# pc_kalam_v3.net
KiCad netlist of a schematic drawn in EAGLE
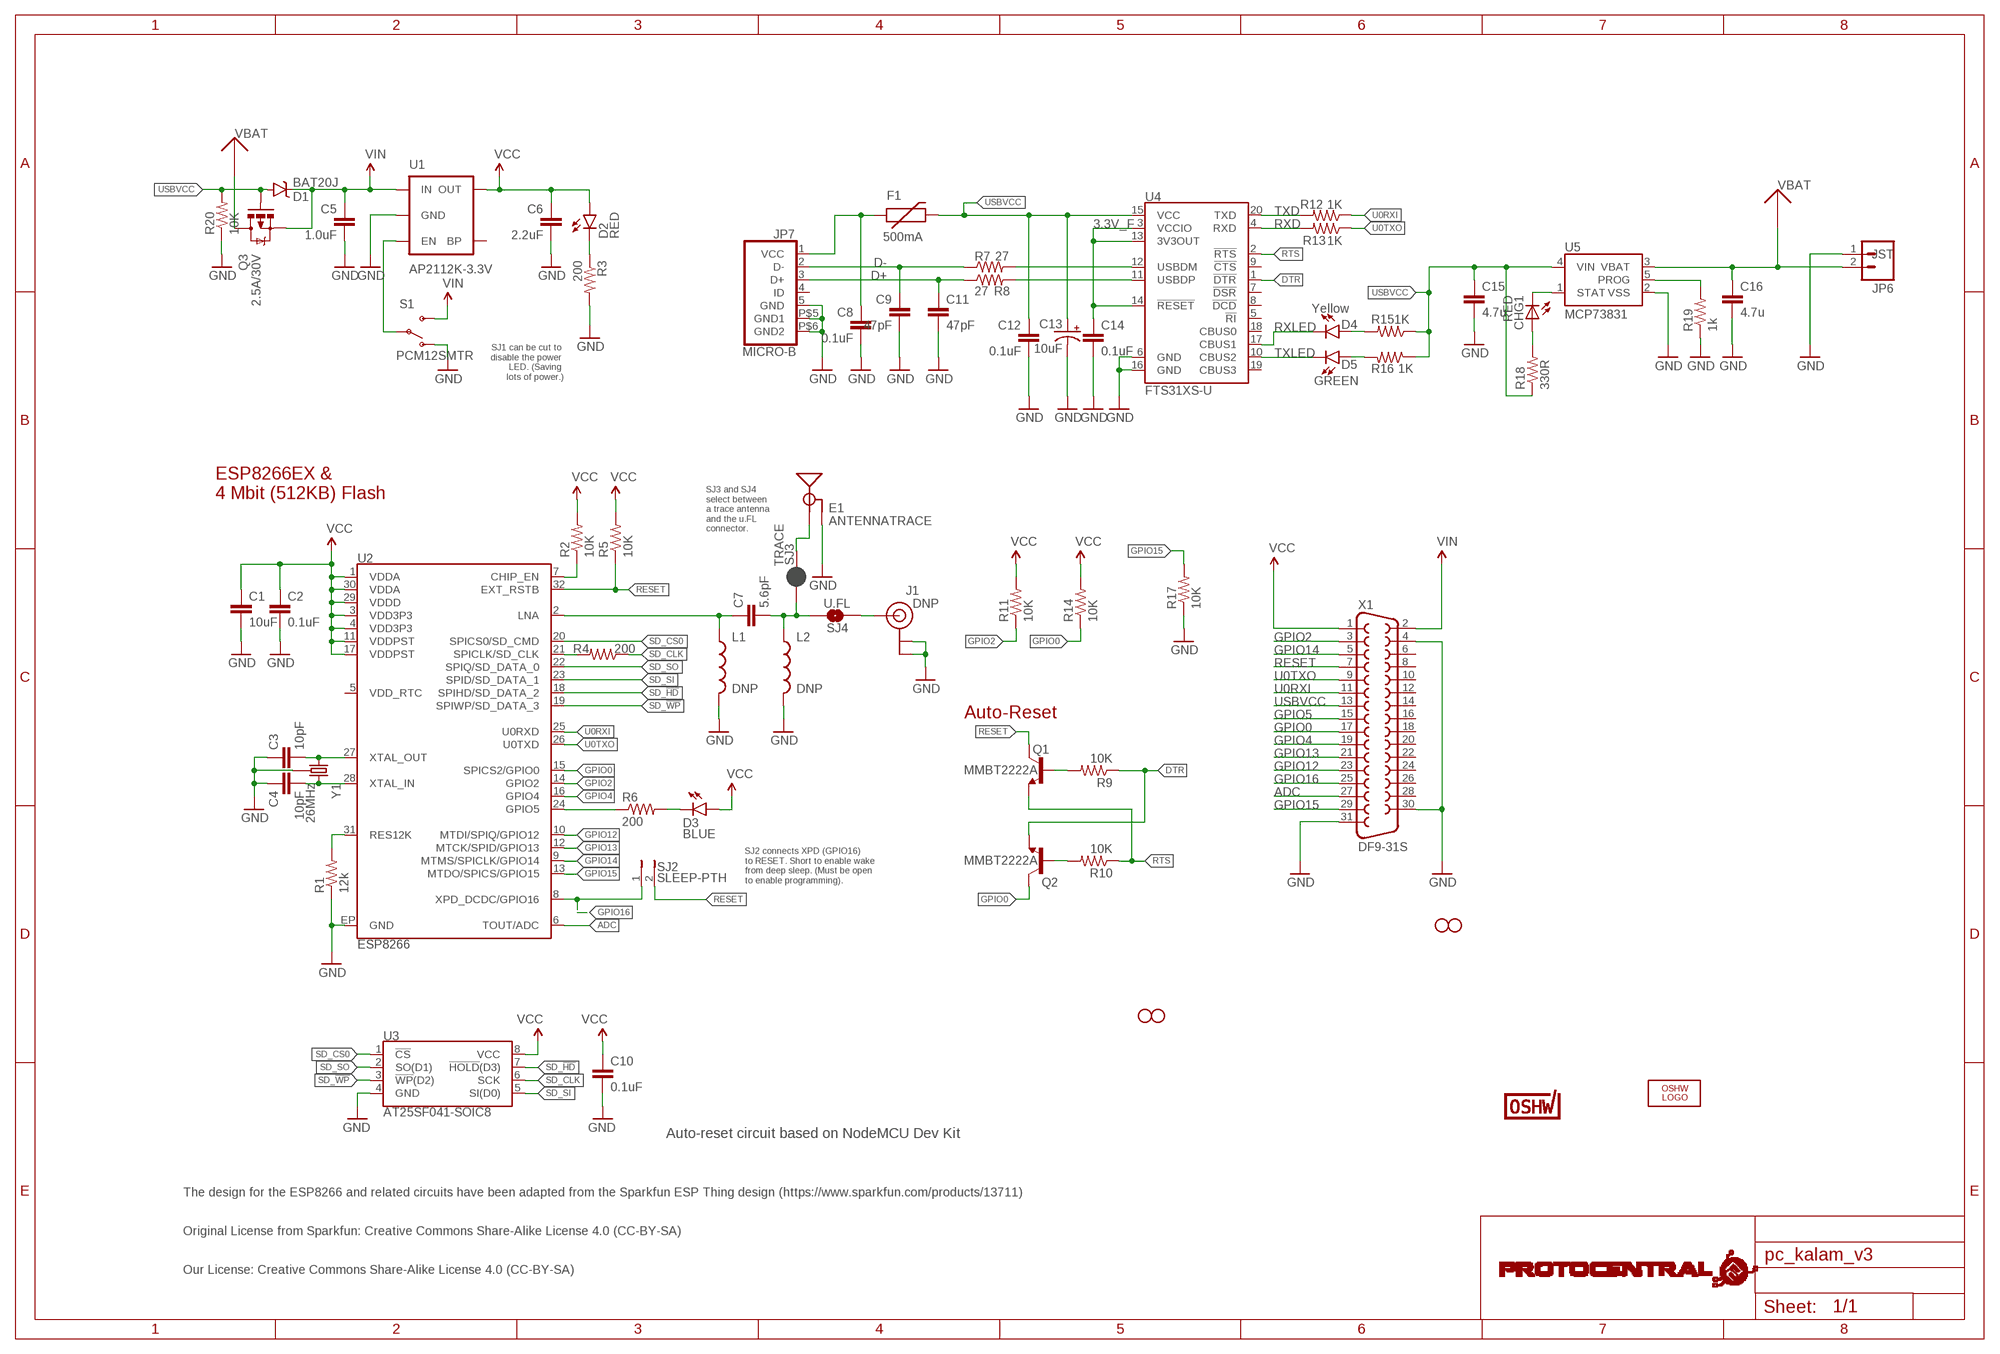
[diagram p0: schematic, sheet 1]

(export (version "E")
  (design (tool "Eeschema 10.0.6"))
  (components
    (comp (ref "C1")
      (value "10uF")
      (footprint "eagle-import:0603-CAP")
      (libsource (lib "eagle-import") (part "10UF-6.3V-20%(0603)"))
    )
    (comp (ref "C2")
      (value "0.1uF")
      (footprint "eagle-import:0603-CAP")
      (libsource (lib "eagle-import") (part "0.1UF-25V(+80/-20%)(0603)"))
    )
    (comp (ref "C3")
      (value "10pF")
      (footprint "eagle-import:0603-CAP")
      (libsource (lib "eagle-import") (part "10PF-50V-5%(0603)"))
    )
    (comp (ref "C4")
      (value "10pF")
      (footprint "eagle-import:0603-CAP")
      (libsource (lib "eagle-import") (part "10PF-50V-5%(0603)"))
    )
    (comp (ref "C5")
      (value "1.0uF")
      (footprint "eagle-import:0805")
      (libsource (lib "eagle-import") (part "1.0UF-25V-+80/-20(0805)"))
    )
    (comp (ref "C6")
      (value "2.2uF")
      (footprint "eagle-import:0603-CAP")
      (libsource (lib "eagle-import") (part "2.2UF-10V-20%(0603)"))
    )
    (comp (ref "C7")
      (value "5.6pF")
      (footprint "eagle-import:0603-CAP")
      (libsource (lib "eagle-import") (part "CAP0603-CAP"))
    )
    (comp (ref "C8")
      (value "0.1uF")
      (footprint "eagle-import:C0402")
      (libsource (lib "eagle-import") (part "C-EUC0402"))
    )
    (comp (ref "C9")
      (value "47pF")
      (footprint "eagle-import:0603-CAP")
      (libsource (lib "eagle-import") (part "47PF-50V-5%(0603)"))
    )
    (comp (ref "C10")
      (value "0.1uF")
      (footprint "eagle-import:0603-CAP")
      (libsource (lib "eagle-import") (part "0.1UF-25V(+80/-20%)(0603)"))
    )
    (comp (ref "C11")
      (value "47pF")
      (footprint "eagle-import:0603-CAP")
      (libsource (lib "eagle-import") (part "47PF-50V-5%(0603)"))
    )
    (comp (ref "C12")
      (value "0.1uF")
      (footprint "eagle-import:0603-CAP")
      (libsource (lib "eagle-import") (part "0.1UF-25V(+80/-20%)(0603)"))
    )
    (comp (ref "C13")
      (value "10uF")
      (footprint "eagle-import:EIA3216")
      (libsource (lib "eagle-import") (part "10UF-16V-10%(TANT)"))
    )
    (comp (ref "C14")
      (value "0.1uF")
      (footprint "eagle-import:0603-CAP")
      (libsource (lib "eagle-import") (part "0.1UF-25V(+80/-20%)(0603)"))
    )
    (comp (ref "C15")
      (value "4.7u")
      (footprint "eagle-import:C0805")
      (libsource (lib "eagle-import") (part "C-EUC0805"))
    )
    (comp (ref "C16")
      (value "4.7u")
      (footprint "eagle-import:C0805")
      (libsource (lib "eagle-import") (part "C-EUC0805"))
    )
    (comp (ref "CHG1")
      (value "RED")
      (footprint "eagle-import:CHIPLED_0603")
      (libsource (lib "eagle-import") (part "LEDCHIPLED_0603"))
    )
    (comp (ref "D1")
      (value "BAT20J")
      (footprint "eagle-import:SOD-323")
      (libsource (lib "eagle-import") (part "DIODE-SCHOTTKY-BAT20J"))
    )
    (comp (ref "D2")
      (value "RED")
      (footprint "eagle-import:LED-0603")
      (libsource (lib "eagle-import") (part "LED-RED0603"))
    )
    (comp (ref "D3")
      (value "BLUE")
      (footprint "eagle-import:LED-0603")
      (libsource (lib "eagle-import") (part "LED-BLUE0603"))
    )
    (comp (ref "D4")
      (value "Yellow")
      (footprint "eagle-import:LED-0603")
      (libsource (lib "eagle-import") (part "LED-YELLOW0603"))
    )
    (comp (ref "D5")
      (value "GREEN")
      (footprint "eagle-import:LED-0603")
      (libsource (lib "eagle-import") (part "LED-GREEN0603"))
    )
    (comp (ref "E1")
      (value "ANTENNATRACE")
      (footprint "eagle-import:TRACE_ANTENNA_2.4GHZ_25.7MM")
      (libsource (lib "eagle-import") (part "ANTENNATRACE"))
    )
    (comp (ref "F1")
      (value "500mA")
      (footprint "eagle-import:PTC-1206")
      (libsource (lib "eagle-import") (part "PTCSMD"))
    )
    (comp (ref "J1")
      (value "DNP")
      (footprint "eagle-import:U.FL")
      (libsource (lib "eagle-import") (part "U.FL"))
    )
    (comp (ref "JP6")
      (value "M02-JST-2MM-SMT")
      (footprint "eagle-import:JST-2-SMD")
      (libsource (lib "eagle-import") (part "M02-JST-2MM-SMT"))
    )
    (comp (ref "JP7")
      (value "MICRO-B")
      (footprint "eagle-import:MICRO-B")
      (libsource (lib "eagle-import") (part "MICRO-B"))
    )
    (comp (ref "L1")
      (value "DNP")
      (footprint "eagle-import:0603")
      (libsource (lib "eagle-import") (part "INDUCTOR0603"))
    )
    (comp (ref "L2")
      (value "DNP")
      (footprint "eagle-import:0603")
      (libsource (lib "eagle-import") (part "INDUCTOR0603"))
    )
    (comp (ref "LOGO2")
      (value "OSHW_LOGO_FILLX0200-NT")
      (footprint "eagle-import:OSHW_FILLX200_NOTEXT")
      (libsource (lib "eagle-import") (part "OSHW_LOGO_FILLX0200-NT"))
    )
    (comp (ref "Q1")
      (value "MMBT2222A")
      (footprint "eagle-import:SOT23-3@1")
      (libsource (lib "eagle-import") (part "TRANSISTOR_NPNMMBT2222A"))
    )
    (comp (ref "Q2")
      (value "MMBT2222A")
      (footprint "eagle-import:SOT23-3@1")
      (libsource (lib "eagle-import") (part "TRANSISTOR_NPNMMBT2222A"))
    )
    (comp (ref "Q3")
      (value "2.5A/30V")
      (footprint "eagle-import:SOT23-3")
      (libsource (lib "eagle-import") (part "MOSFET-PCHANNELDMG2307L"))
    )
    (comp (ref "R1")
      (value "12k")
      (footprint "eagle-import:0603-RES")
      (libsource (lib "eagle-import") (part "12KOHM-1/10W-1%(0603)"))
    )
    (comp (ref "R2")
      (value "10K")
      (footprint "eagle-import:0603-RES")
      (libsource (lib "eagle-import") (part "10KOHM1/10W1%(0603)0603"))
    )
    (comp (ref "R3")
      (value "200")
      (footprint "eagle-import:0603-RES")
      (libsource (lib "eagle-import") (part "200OHM1/10W1%(0603)"))
    )
    (comp (ref "R4")
      (value "200")
      (footprint "eagle-import:0603-RES")
      (libsource (lib "eagle-import") (part "200OHM1/10W1%(0603)"))
    )
    (comp (ref "R5")
      (value "10K")
      (footprint "eagle-import:0603-RES")
      (libsource (lib "eagle-import") (part "10KOHM1/10W1%(0603)0603"))
    )
    (comp (ref "R6")
      (value "200")
      (footprint "eagle-import:0603-RES")
      (libsource (lib "eagle-import") (part "200OHM1/10W1%(0603)"))
    )
    (comp (ref "R7")
      (value "27")
      (footprint "eagle-import:0603-RES")
      (libsource (lib "eagle-import") (part "27OHM1/10W1%(0603)0603-RES"))
    )
    (comp (ref "R8")
      (value "27")
      (footprint "eagle-import:0603-RES")
      (libsource (lib "eagle-import") (part "27OHM1/10W1%(0603)0603-RES"))
    )
    (comp (ref "R9")
      (value "10K")
      (footprint "eagle-import:0603-RES")
      (libsource (lib "eagle-import") (part "10KOHM1/10W1%(0603)0603"))
    )
    (comp (ref "R10")
      (value "10K")
      (footprint "eagle-import:0603-RES")
      (libsource (lib "eagle-import") (part "10KOHM1/10W1%(0603)0603"))
    )
    (comp (ref "R11")
      (value "10K")
      (footprint "eagle-import:0603-RES")
      (libsource (lib "eagle-import") (part "10KOHM1/10W1%(0603)0603"))
    )
    (comp (ref "R12")
      (value "1K")
      (footprint "eagle-import:0603-RES")
      (libsource (lib "eagle-import") (part "1KOHM-1/10W-1%(0603)"))
    )
    (comp (ref "R13")
      (value "1K")
      (footprint "eagle-import:0603-RES")
      (libsource (lib "eagle-import") (part "1KOHM-1/10W-1%(0603)"))
    )
    (comp (ref "R14")
      (value "10K")
      (footprint "eagle-import:0603-RES")
      (libsource (lib "eagle-import") (part "10KOHM1/10W1%(0603)0603"))
    )
    (comp (ref "R15")
      (value "1K")
      (footprint "eagle-import:0603-RES")
      (libsource (lib "eagle-import") (part "1KOHM-1/10W-1%(0603)"))
    )
    (comp (ref "R16")
      (value "1K")
      (footprint "eagle-import:0603-RES")
      (libsource (lib "eagle-import") (part "1KOHM-1/10W-1%(0603)"))
    )
    (comp (ref "R17")
      (value "10K")
      (footprint "eagle-import:0603-RES")
      (libsource (lib "eagle-import") (part "10KOHM1/10W1%(0603)0603"))
    )
    (comp (ref "R18")
      (value "330R")
      (footprint "eagle-import:R0402")
      (libsource (lib "eagle-import") (part "R-US_R0402"))
    )
    (comp (ref "R19")
      (value "1k")
      (footprint "eagle-import:R0402")
      (libsource (lib "eagle-import") (part "R-US_R0402"))
    )
    (comp (ref "R20")
      (value "10K")
      (footprint "eagle-import:R0402")
      (libsource (lib "eagle-import") (part "R-US_R0402"))
    )
    (comp (ref "S1")
      (value "PCM12SMTR")
      (footprint "eagle-import:SWITCH-SPST-SMD-A")
      (libsource (lib "eagle-import") (part "SWITCH-SPDT-SMD-A"))
    )
    (comp (ref "SJ2")
      (value "SLEEP-PTH")
      (footprint "eagle-import:PTH-JUMPER-2-NO_NO_SILK")
      (libsource (lib "eagle-import") (part "JUMPER-PTH-2-NO"))
    )
    (comp (ref "SJ3")
      (value "TRACE")
      (footprint "eagle-import:PAD-JUMPER-2-NC_BY_PASTE_NO_SILK")
      (libsource (lib "eagle-import") (part "JUMPER-PAD-2-NC_BY_PASTENO-SILK"))
    )
    (comp (ref "SJ4")
      (value "U.FL")
      (footprint "eagle-import:PAD-JUMPER-2-NO_NO_SILK")
      (libsource (lib "eagle-import") (part "JUMPER-PAD-2-NO"))
    )
    (comp (ref "STANDOFF1")
      (value "STAND-OFF")
      (footprint "eagle-import:STAND-OFF")
      (libsource (lib "eagle-import") (part "STAND-OFF"))
    )
    (comp (ref "STANDOFF2")
      (value "STAND-OFF")
      (footprint "eagle-import:STAND-OFF")
      (libsource (lib "eagle-import") (part "STAND-OFF"))
    )
    (comp (ref "STANDOFF3")
      (value "STAND-OFF")
      (footprint "eagle-import:STAND-OFF")
      (libsource (lib "eagle-import") (part "STAND-OFF"))
    )
    (comp (ref "STANDOFF4")
      (value "STAND-OFF")
      (footprint "eagle-import:STAND-OFF")
      (libsource (lib "eagle-import") (part "STAND-OFF"))
    )
    (comp (ref "U$1")
      (value "PROTY_LOGO_WITH_TEXT")
      (footprint "eagle-import:PROTY_WITH_TEXT")
      (libsource (lib "eagle-import") (part "PROTY_LOGO_WITH_TEXT"))
    )
    (comp (ref "U$5")
      (value "CERT-MEDIUM")
      (footprint "eagle-import:CERT-MED-SILK")
      (libsource (lib "eagle-import") (part "CERT-MEDIUM"))
    )
    (comp (ref "U$8")
      (value "PROTY-LOGO")
      (footprint "eagle-import:LOGO-PROTY")
      (libsource (lib "eagle-import") (part "PROTY-LOGO"))
    )
    (comp (ref "U1")
      (value "AP2112K-3.3V")
      (footprint "eagle-import:SOT23-5")
      (libsource (lib "eagle-import") (part "V_REG_LDOSMD"))
    )
    (comp (ref "U2")
      (value "ESP8266")
      (footprint "eagle-import:QFN32")
      (libsource (lib "eagle-import") (part "ESP8266"))
    )
    (comp (ref "U3")
      (value "AT25SF041-SOIC8")
      (footprint "eagle-import:SO08")
      (libsource (lib "eagle-import") (part "AT25SF041-SOIC8"))
    )
    (comp (ref "U4")
      (value "FTS31XS-U")
      (footprint "eagle-import:SSOP20_L")
      (libsource (lib "eagle-import") (part "FT231XS"))
    )
    (comp (ref "U5")
      (value "MCP73831")
      (footprint "eagle-import:SOT23-5")
      (libsource (lib "eagle-import") (part "MCP73831"))
    )
    (comp (ref "X1")
      (value "DF9-31S")
      (footprint "eagle-import:DF9-31S")
      (fields (field (name "MPN") "DF9-31S-1V(32)"))
      (libsource (lib "eagle-import") (part "DF9-31S"))
    )
    (comp (ref "Y1")
      (value "26MHz")
      (footprint "eagle-import:CRYSTAL-SMD-3.2X2.5")
      (libsource (lib "eagle-import") (part "CRYSTAL-GROUNDED3.2X2.5"))
    )
  )
  (nets
    (net (code "1") (name "/3.3V_F") (class "Default")
      (node (ref "C14") (pin "1") (pinfunction "1_1") (pintype "passive"))
      (node (ref "U4") (pin "13") (pinfunction "3V3OUT_13") (pintype "bidirectional"))
      (node (ref "U4") (pin "14") (pinfunction "~{RESET}_14") (pintype "bidirectional"))
      (node (ref "U4") (pin "3") (pinfunction "VCCIO_3") (pintype "bidirectional"))
    )
    (net (code "2") (name "/D+") (class "Default")
      (node (ref "C11") (pin "1") (pinfunction "1_1") (pintype "passive"))
      (node (ref "JP7") (pin "3") (pinfunction "D+_3") (pintype "bidirectional"))
      (node (ref "R8") (pin "1") (pinfunction "1_1") (pintype "passive"))
    )
    (net (code "3") (name "/D-") (class "Default")
      (node (ref "C9") (pin "1") (pinfunction "1_1") (pintype "passive"))
      (node (ref "JP7") (pin "2") (pinfunction "D-_2") (pintype "bidirectional"))
      (node (ref "R7") (pin "1") (pinfunction "1_1") (pintype "passive"))
    )
    (net (code "4") (name "/GPIO5") (class "Default")
      (node (ref "R6") (pin "1") (pinfunction "1_1") (pintype "passive"))
      (node (ref "U2") (pin "24") (pinfunction "GPIO5_24") (pintype "bidirectional"))
      (node (ref "X1") (pin "15") (pinfunction "15_15") (pintype "passive"))
    )
    (net (code "5") (name "/RXD") (class "Default")
      (node (ref "R13") (pin "2") (pinfunction "2_2") (pintype "passive"))
      (node (ref "U4") (pin "4") (pinfunction "RXD_4") (pintype "bidirectional"))
    )
    (net (code "6") (name "/RXLED") (class "Default")
      (node (ref "D4") (pin "C") (pinfunction "C_C") (pintype "passive"))
      (node (ref "U4") (pin "17") (pinfunction "CBUS1_17") (pintype "bidirectional"))
    )
    (net (code "7") (name "/SD_~{HD}") (class "Default")
      (node (ref "U2") (pin "18") (pinfunction "SPIHD/SD_DATA_2_18") (pintype "bidirectional"))
      (node (ref "U3") (pin "7") (pinfunction "~{HOLD}(D3)_7") (pintype "bidirectional"))
    )
    (net (code "8") (name "/SD_~{WP}") (class "Default")
      (node (ref "U2") (pin "19") (pinfunction "SPIWP/SD_DATA_3_19") (pintype "bidirectional"))
      (node (ref "U3") (pin "3") (pinfunction "~{WP}(D2)_3") (pintype "bidirectional"))
    )
    (net (code "9") (name "/TXD") (class "Default")
      (node (ref "R12") (pin "2") (pinfunction "2_2") (pintype "passive"))
      (node (ref "U4") (pin "20") (pinfunction "TXD_20") (pintype "bidirectional"))
    )
    (net (code "10") (name "/TXLED") (class "Default")
      (node (ref "D5") (pin "C") (pinfunction "C_C") (pintype "passive"))
      (node (ref "U4") (pin "10") (pinfunction "CBUS2_10") (pintype "bidirectional"))
    )
    (net (code "11") (name "ADC") (class "Default")
      (node (ref "U2") (pin "6") (pinfunction "TOUT/ADC_6") (pintype "bidirectional"))
      (node (ref "X1") (pin "27") (pinfunction "27_27") (pintype "passive"))
    )
    (net (code "12") (name "DTR") (class "Default")
      (node (ref "Q2") (pin "2") (pinfunction "E_2") (pintype "passive"))
      (node (ref "R9") (pin "1") (pinfunction "1_1") (pintype "passive"))
      (node (ref "U4") (pin "1") (pinfunction "~{DTR}_1") (pintype "bidirectional"))
    )
    (net (code "13") (name "GND") (class "Default")
      (node (ref "C1") (pin "2") (pinfunction "2_2") (pintype "passive"))
      (node (ref "C10") (pin "2") (pinfunction "2_2") (pintype "passive"))
      (node (ref "C11") (pin "2") (pinfunction "2_2") (pintype "passive"))
      (node (ref "C12") (pin "2") (pinfunction "2_2") (pintype "passive"))
      (node (ref "C13") (pin "C") (pinfunction "-_C") (pintype "passive"))
      (node (ref "C14") (pin "2") (pinfunction "2_2") (pintype "passive"))
      (node (ref "C15") (pin "2") (pinfunction "2_2") (pintype "passive"))
      (node (ref "C16") (pin "2") (pinfunction "2_2") (pintype "passive"))
      (node (ref "C2") (pin "2") (pinfunction "2_2") (pintype "passive"))
      (node (ref "C3") (pin "1") (pinfunction "1_1") (pintype "passive"))
      (node (ref "C4") (pin "1") (pinfunction "1_1") (pintype "passive"))
      (node (ref "C5") (pin "2") (pinfunction "2_2") (pintype "passive"))
      (node (ref "C6") (pin "2") (pinfunction "2_2") (pintype "passive"))
      (node (ref "C8") (pin "2") (pinfunction "2_2") (pintype "passive"))
      (node (ref "C9") (pin "2") (pinfunction "2_2") (pintype "passive"))
      (node (ref "E1") (pin "GND") (pinfunction "GND_GND") (pintype "bidirectional"))
      (node (ref "E1") (pin "GND2") (pinfunction "GND_GND2") (pintype "bidirectional"))
      (node (ref "J1") (pin "P$1") (pinfunction "GND_P$1") (pintype "bidirectional"))
      (node (ref "J1") (pin "P$2") (pinfunction "GND_P$2") (pintype "bidirectional"))
      (node (ref "JP6") (pin "1") (pinfunction "1_1") (pintype "passive"))
      (node (ref "JP7") (pin "5") (pinfunction "GND_5") (pintype "bidirectional"))
      (node (ref "JP7") (pin "P$5") (pinfunction "GND1_P$5") (pintype "bidirectional"))
      (node (ref "JP7") (pin "P$6") (pinfunction "GND2_P$6") (pintype "bidirectional"))
      (node (ref "L1") (pin "2") (pinfunction "2_2") (pintype "passive"))
      (node (ref "L2") (pin "2") (pinfunction "2_2") (pintype "passive"))
      (node (ref "R1") (pin "1") (pinfunction "1_1") (pintype "passive"))
      (node (ref "R17") (pin "1") (pinfunction "1_1") (pintype "passive"))
      (node (ref "R19") (pin "1") (pinfunction "1_1") (pintype "passive"))
      (node (ref "R20") (pin "1") (pinfunction "1_1") (pintype "passive"))
      (node (ref "R3") (pin "2") (pinfunction "2_2") (pintype "passive"))
      (node (ref "S1") (pin "1") (pinfunction "O_1") (pintype "passive"))
      (node (ref "U1") (pin "2") (pinfunction "GND_2") (pintype "input"))
      (node (ref "U2") (pin "EP") (pinfunction "GND_EP") (pintype "bidirectional"))
      (node (ref "U3") (pin "4") (pinfunction "GND_4") (pintype "bidirectional"))
      (node (ref "U4") (pin "16") (pinfunction "GND_16") (pintype "bidirectional"))
      (node (ref "U4") (pin "6") (pinfunction "GND_6") (pintype "bidirectional"))
      (node (ref "U5") (pin "2") (pinfunction "VSS_2") (pintype "power_in"))
      (node (ref "X1") (pin "30") (pinfunction "30_30") (pintype "passive"))
      (node (ref "X1") (pin "31") (pinfunction "31_31") (pintype "passive"))
      (node (ref "X1") (pin "4") (pinfunction "4_4") (pintype "passive"))
      (node (ref "Y1") (pin "2") (pinfunction "GND_2") (pintype "passive"))
      (node (ref "Y1") (pin "4") (pinfunction "GND_4") (pintype "passive"))
    )
    (net (code "14") (name "GPIO0") (class "Default")
      (node (ref "Q2") (pin "3") (pinfunction "C_3") (pintype "passive"))
      (node (ref "R14") (pin "1") (pinfunction "1_1") (pintype "passive"))
      (node (ref "U2") (pin "15") (pinfunction "SPICS2/GPIO0_15") (pintype "bidirectional"))
      (node (ref "X1") (pin "17") (pinfunction "17_17") (pintype "passive"))
    )
    (net (code "15") (name "GPIO2") (class "Default")
      (node (ref "R11") (pin "1") (pinfunction "1_1") (pintype "passive"))
      (node (ref "U2") (pin "14") (pinfunction "GPIO2_14") (pintype "bidirectional"))
      (node (ref "X1") (pin "3") (pinfunction "3_3") (pintype "passive"))
    )
    (net (code "16") (name "GPIO4") (class "Default")
      (node (ref "U2") (pin "16") (pinfunction "GPIO4_16") (pintype "bidirectional"))
      (node (ref "X1") (pin "19") (pinfunction "19_19") (pintype "passive"))
    )
    (net (code "17") (name "GPIO12") (class "Default")
      (node (ref "U2") (pin "10") (pinfunction "MTDI/SPIQ/GPIO12_10") (pintype "bidirectional"))
      (node (ref "X1") (pin "23") (pinfunction "23_23") (pintype "passive"))
    )
    (net (code "18") (name "GPIO13") (class "Default")
      (node (ref "U2") (pin "12") (pinfunction "MTCK/SPID/GPIO13_12") (pintype "bidirectional"))
      (node (ref "X1") (pin "21") (pinfunction "21_21") (pintype "passive"))
    )
    (net (code "19") (name "GPIO14") (class "Default")
      (node (ref "U2") (pin "9") (pinfunction "MTMS/SPICLK/GPIO14_9") (pintype "bidirectional"))
      (node (ref "X1") (pin "5") (pinfunction "5_5") (pintype "passive"))
    )
    (net (code "20") (name "GPIO15") (class "Default")
      (node (ref "R17") (pin "2") (pinfunction "2_2") (pintype "passive"))
      (node (ref "U2") (pin "13") (pinfunction "MTDO/SPICS/GPIO15_13") (pintype "bidirectional"))
      (node (ref "X1") (pin "29") (pinfunction "29_29") (pintype "passive"))
    )
    (net (code "21") (name "GPIO16") (class "Default")
      (node (ref "SJ2") (pin "1") (pinfunction "1_1") (pintype "passive"))
      (node (ref "U2") (pin "8") (pinfunction "XPD_DCDC/GPIO16_8") (pintype "bidirectional"))
      (node (ref "X1") (pin "25") (pinfunction "25_25") (pintype "passive"))
    )
    (net (code "22") (name "Net-(C7-Pad2)") (class "Default")
      (node (ref "C7") (pin "2") (pinfunction "2_2") (pintype "passive"))
      (node (ref "L2") (pin "1") (pinfunction "1_1") (pintype "passive"))
      (node (ref "SJ3") (pin "1") (pinfunction "1_1") (pintype "passive"))
      (node (ref "SJ4") (pin "2") (pinfunction "2_2") (pintype "passive"))
    )
    (net (code "23") (name "Net-(CHG1-PadA)") (class "Default")
      (node (ref "CHG1") (pin "A") (pinfunction "A_A") (pintype "passive"))
      (node (ref "R18") (pin "2") (pinfunction "2_2") (pintype "passive"))
    )
    (net (code "24") (name "Net-(D2-PadC)") (class "Default")
      (node (ref "D2") (pin "C") (pinfunction "C_C") (pintype "passive"))
      (node (ref "R3") (pin "1") (pinfunction "1_1") (pintype "passive"))
    )
    (net (code "25") (name "Net-(D3-PadC)") (class "Default")
      (node (ref "D3") (pin "C") (pinfunction "C_C") (pintype "passive"))
      (node (ref "R6") (pin "2") (pinfunction "2_2") (pintype "passive"))
    )
    (net (code "26") (name "Net-(D4-PadA)") (class "Default")
      (node (ref "D4") (pin "A") (pinfunction "A_A") (pintype "passive"))
      (node (ref "R15") (pin "2") (pinfunction "2_2") (pintype "passive"))
    )
    (net (code "27") (name "Net-(D5-PadA)") (class "Default")
      (node (ref "D5") (pin "A") (pinfunction "A_A") (pintype "passive"))
      (node (ref "R16") (pin "2") (pinfunction "2_2") (pintype "passive"))
    )
    (net (code "28") (name "Net-(E1-SIGNAL)") (class "Default")
      (node (ref "E1") (pin "ANT") (pinfunction "SIGNAL_ANT") (pintype "bidirectional"))
      (node (ref "SJ3") (pin "2") (pinfunction "2_2") (pintype "passive"))
    )
    (net (code "29") (name "Net-(J1-SIGNAL)") (class "Default")
      (node (ref "J1") (pin "P$3") (pinfunction "SIGNAL_P$3") (pintype "bidirectional"))
      (node (ref "SJ4") (pin "1") (pinfunction "1_1") (pintype "passive"))
    )
    (net (code "30") (name "Net-(JP7-VCC)") (class "Default")
      (node (ref "C8") (pin "1") (pinfunction "1_1") (pintype "passive"))
      (node (ref "F1") (pin "1") (pinfunction "1_1") (pintype "bidirectional"))
      (node (ref "JP7") (pin "1") (pinfunction "VCC_1") (pintype "bidirectional"))
    )
    (net (code "31") (name "Net-(Q1-B)") (class "Default")
      (node (ref "Q1") (pin "1") (pinfunction "B_1") (pintype "passive"))
      (node (ref "R9") (pin "2") (pinfunction "2_2") (pintype "passive"))
    )
    (net (code "32") (name "Net-(Q2-B)") (class "Default")
      (node (ref "Q2") (pin "1") (pinfunction "B_1") (pintype "passive"))
      (node (ref "R10") (pin "2") (pinfunction "2_2") (pintype "passive"))
    )
    (net (code "33") (name "Net-(S1-P)") (class "Default")
      (node (ref "S1") (pin "2") (pinfunction "P_2") (pintype "passive"))
      (node (ref "U1") (pin "3") (pinfunction "EN_3") (pintype "input"))
    )
    (net (code "34") (name "Net-(U2-CHIP_EN)") (class "Default")
      (node (ref "R2") (pin "1") (pinfunction "1_1") (pintype "passive"))
      (node (ref "U2") (pin "7") (pinfunction "CHIP_EN_7") (pintype "bidirectional"))
    )
    (net (code "35") (name "Net-(U2-LNA)") (class "Default")
      (node (ref "C7") (pin "1") (pinfunction "1_1") (pintype "passive"))
      (node (ref "L1") (pin "1") (pinfunction "1_1") (pintype "passive"))
      (node (ref "U2") (pin "2") (pinfunction "LNA_2") (pintype "bidirectional"))
    )
    (net (code "36") (name "Net-(U2-RES12K)") (class "Default")
      (node (ref "R1") (pin "2") (pinfunction "2_2") (pintype "passive"))
      (node (ref "U2") (pin "31") (pinfunction "RES12K_31") (pintype "bidirectional"))
    )
    (net (code "37") (name "Net-(U2-SPICLK{slash}SD_CLK)") (class "Default")
      (node (ref "R4") (pin "2") (pinfunction "2_2") (pintype "passive"))
      (node (ref "U2") (pin "21") (pinfunction "SPICLK/SD_CLK_21") (pintype "bidirectional"))
    )
    (net (code "38") (name "Net-(U2-XTAL_IN)") (class "Default")
      (node (ref "C4") (pin "2") (pinfunction "2_2") (pintype "passive"))
      (node (ref "U2") (pin "28") (pinfunction "XTAL_IN_28") (pintype "bidirectional"))
      (node (ref "Y1") (pin "3") (pinfunction "2_3") (pintype "passive"))
    )
    (net (code "39") (name "Net-(U2-XTAL_OUT)") (class "Default")
      (node (ref "C3") (pin "2") (pinfunction "2_2") (pintype "passive"))
      (node (ref "U2") (pin "27") (pinfunction "XTAL_OUT_27") (pintype "bidirectional"))
      (node (ref "Y1") (pin "1") (pinfunction "1_1") (pintype "passive"))
    )
    (net (code "40") (name "Net-(U4-USBDM)") (class "Default")
      (node (ref "R7") (pin "2") (pinfunction "2_2") (pintype "passive"))
      (node (ref "U4") (pin "12") (pinfunction "USBDM_12") (pintype "bidirectional"))
    )
    (net (code "41") (name "Net-(U4-USBDP)") (class "Default")
      (node (ref "R8") (pin "2") (pinfunction "2_2") (pintype "passive"))
      (node (ref "U4") (pin "11") (pinfunction "USBDP_11") (pintype "bidirectional"))
    )
    (net (code "42") (name "Net-(U5-PROG)") (class "Default")
      (node (ref "R19") (pin "2") (pinfunction "2_2") (pintype "passive"))
      (node (ref "U5") (pin "5") (pinfunction "PROG_5") (pintype "input"))
    )
    (net (code "43") (name "Net-(U5-STAT)") (class "Default")
      (node (ref "CHG1") (pin "C") (pinfunction "C_C") (pintype "passive"))
      (node (ref "U5") (pin "1") (pinfunction "STAT_1") (pintype "output"))
    )
    (net (code "44") (name "RESET") (class "Default")
      (node (ref "Q1") (pin "3") (pinfunction "C_3") (pintype "passive"))
      (node (ref "R5") (pin "1") (pinfunction "1_1") (pintype "passive"))
      (node (ref "SJ2") (pin "2") (pinfunction "2_2") (pintype "passive"))
      (node (ref "U2") (pin "32") (pinfunction "EXT_RSTB_32") (pintype "bidirectional"))
      (node (ref "X1") (pin "7") (pinfunction "7_7") (pintype "passive"))
    )
    (net (code "45") (name "RTS") (class "Default")
      (node (ref "Q1") (pin "2") (pinfunction "E_2") (pintype "passive"))
      (node (ref "R10") (pin "1") (pinfunction "1_1") (pintype "passive"))
      (node (ref "U4") (pin "2") (pinfunction "~{RTS}_2") (pintype "bidirectional"))
    )
    (net (code "46") (name "SD_CLK") (class "Default")
      (node (ref "R4") (pin "1") (pinfunction "1_1") (pintype "passive"))
      (node (ref "U3") (pin "6") (pinfunction "SCK_6") (pintype "bidirectional"))
    )
    (net (code "47") (name "SD_CS0") (class "Default")
      (node (ref "U2") (pin "20") (pinfunction "SPICS0/SD_CMD_20") (pintype "bidirectional"))
      (node (ref "U3") (pin "1") (pinfunction "~{CS}_1") (pintype "bidirectional"))
    )
    (net (code "48") (name "SD_SI") (class "Default")
      (node (ref "U2") (pin "23") (pinfunction "SPID/SD_DATA_1_23") (pintype "bidirectional"))
      (node (ref "U3") (pin "5") (pinfunction "SI(D0)_5") (pintype "bidirectional"))
    )
    (net (code "49") (name "SD_SO") (class "Default")
      (node (ref "U2") (pin "22") (pinfunction "SPIQ/SD_DATA_0_22") (pintype "bidirectional"))
      (node (ref "U3") (pin "2") (pinfunction "SO(D1)_2") (pintype "bidirectional"))
    )
    (net (code "50") (name "U0RXI") (class "Default")
      (node (ref "R12") (pin "1") (pinfunction "1_1") (pintype "passive"))
      (node (ref "U2") (pin "25") (pinfunction "U0RXD_25") (pintype "bidirectional"))
      (node (ref "X1") (pin "11") (pinfunction "11_11") (pintype "passive"))
    )
    (net (code "51") (name "U0TXO") (class "Default")
      (node (ref "R13") (pin "1") (pinfunction "1_1") (pintype "passive"))
      (node (ref "U2") (pin "26") (pinfunction "U0TXD_26") (pintype "bidirectional"))
      (node (ref "X1") (pin "9") (pinfunction "9_9") (pintype "passive"))
    )
    (net (code "52") (name "USBVCC") (class "Default")
      (node (ref "C12") (pin "1") (pinfunction "1_1") (pintype "passive"))
      (node (ref "C13") (pin "A") (pinfunction "+_A") (pintype "passive"))
      (node (ref "C15") (pin "1") (pinfunction "1_1") (pintype "passive"))
      (node (ref "D1") (pin "A") (pinfunction "A_A") (pintype "passive"))
      (node (ref "F1") (pin "2") (pinfunction "2_2") (pintype "bidirectional"))
      (node (ref "Q3") (pin "1") (pinfunction "G_1") (pintype "passive"))
      (node (ref "R15") (pin "1") (pinfunction "1_1") (pintype "passive"))
      (node (ref "R16") (pin "1") (pinfunction "1_1") (pintype "passive"))
      (node (ref "R18") (pin "1") (pinfunction "1_1") (pintype "passive"))
      (node (ref "R20") (pin "2") (pinfunction "2_2") (pintype "passive"))
      (node (ref "U4") (pin "15") (pinfunction "VCC_15") (pintype "bidirectional"))
      (node (ref "U5") (pin "4") (pinfunction "VIN_4") (pintype "power_in"))
      (node (ref "X1") (pin "13") (pinfunction "13_13") (pintype "passive"))
    )
    (net (code "53") (name "VBAT") (class "Default")
      (node (ref "C16") (pin "1") (pinfunction "1_1") (pintype "passive"))
      (node (ref "JP6") (pin "2") (pinfunction "2_2") (pintype "passive"))
      (node (ref "Q3") (pin "3") (pinfunction "D_3") (pintype "passive"))
      (node (ref "U5") (pin "3") (pinfunction "VBAT_3") (pintype "power_in"))
    )
    (net (code "54") (name "VCC") (class "Default")
      (node (ref "C1") (pin "1") (pinfunction "1_1") (pintype "passive"))
      (node (ref "C10") (pin "1") (pinfunction "1_1") (pintype "passive"))
      (node (ref "C2") (pin "1") (pinfunction "1_1") (pintype "passive"))
      (node (ref "C6") (pin "1") (pinfunction "1_1") (pintype "passive"))
      (node (ref "D2") (pin "A") (pinfunction "A_A") (pintype "passive"))
      (node (ref "D3") (pin "A") (pinfunction "A_A") (pintype "passive"))
      (node (ref "R11") (pin "2") (pinfunction "2_2") (pintype "passive"))
      (node (ref "R14") (pin "2") (pinfunction "2_2") (pintype "passive"))
      (node (ref "R2") (pin "2") (pinfunction "2_2") (pintype "passive"))
      (node (ref "R5") (pin "2") (pinfunction "2_2") (pintype "passive"))
      (node (ref "U1") (pin "5") (pinfunction "OUT_5") (pintype "passive"))
      (node (ref "U2") (pin "1") (pinfunction "VDDA_1") (pintype "bidirectional"))
      (node (ref "U2") (pin "11") (pinfunction "VDDPST_11") (pintype "bidirectional"))
      (node (ref "U2") (pin "17") (pinfunction "VDDPST_17") (pintype "bidirectional"))
      (node (ref "U2") (pin "29") (pinfunction "VDDD_29") (pintype "bidirectional"))
      (node (ref "U2") (pin "3") (pinfunction "VDD3P3_3") (pintype "bidirectional"))
      (node (ref "U2") (pin "30") (pinfunction "VDDA_30") (pintype "bidirectional"))
      (node (ref "U2") (pin "4") (pinfunction "VDD3P3_4") (pintype "bidirectional"))
      (node (ref "U3") (pin "8") (pinfunction "VCC_8") (pintype "bidirectional"))
      (node (ref "X1") (pin "1") (pinfunction "1_1") (pintype "passive"))
    )
    (net (code "55") (name "VIN") (class "Default")
      (node (ref "C5") (pin "1") (pinfunction "1_1") (pintype "passive"))
      (node (ref "D1") (pin "C") (pinfunction "C_C") (pintype "passive"))
      (node (ref "Q3") (pin "2") (pinfunction "S_2") (pintype "passive"))
      (node (ref "S1") (pin "3") (pinfunction "S_3") (pintype "passive"))
      (node (ref "U1") (pin "1") (pinfunction "IN_1") (pintype "input"))
      (node (ref "X1") (pin "2") (pinfunction "2_2") (pintype "passive"))
    )
    (net (code "56") (name "unconnected-(JP7-ID-Pad4)") (class "Default")
      (node (ref "JP7") (pin "4") (pinfunction "ID_4") (pintype "bidirectional"))
    )
    (net (code "57") (name "unconnected-(U1-BP-Pad4)") (class "Default")
      (node (ref "U1") (pin "4") (pinfunction "BP_4") (pintype "input"))
    )
    (net (code "58") (name "unconnected-(U2-VDD_RTC-Pad5)") (class "Default")
      (node (ref "U2") (pin "5") (pinfunction "VDD_RTC_5") (pintype "bidirectional"))
    )
    (net (code "59") (name "unconnected-(U4-CBUS0-Pad18)") (class "Default")
      (node (ref "U4") (pin "18") (pinfunction "CBUS0_18") (pintype "bidirectional"))
    )
    (net (code "60") (name "unconnected-(U4-CBUS3-Pad19)") (class "Default")
      (node (ref "U4") (pin "19") (pinfunction "CBUS3_19") (pintype "bidirectional"))
    )
    (net (code "61") (name "unconnected-(U4-~{CTS}-Pad9)") (class "Default")
      (node (ref "U4") (pin "9") (pinfunction "~{CTS}_9") (pintype "bidirectional"))
    )
    (net (code "62") (name "unconnected-(U4-~{DCD}-Pad8)") (class "Default")
      (node (ref "U4") (pin "8") (pinfunction "~{DCD}_8") (pintype "bidirectional"))
    )
    (net (code "63") (name "unconnected-(U4-~{DSR}-Pad7)") (class "Default")
      (node (ref "U4") (pin "7") (pinfunction "~{DSR}_7") (pintype "bidirectional"))
    )
    (net (code "64") (name "unconnected-(U4-~{RI}-Pad5)") (class "Default")
      (node (ref "U4") (pin "5") (pinfunction "~{RI}_5") (pintype "bidirectional"))
    )
    (net (code "65") (name "unconnected-(X1-Pad6)") (class "Default")
      (node (ref "X1") (pin "6") (pinfunction "6_6") (pintype "passive"))
    )
    (net (code "66") (name "unconnected-(X1-Pad8)") (class "Default")
      (node (ref "X1") (pin "8") (pinfunction "8_8") (pintype "passive"))
    )
    (net (code "67") (name "unconnected-(X1-Pad10)") (class "Default")
      (node (ref "X1") (pin "10") (pinfunction "10_10") (pintype "passive"))
    )
    (net (code "68") (name "unconnected-(X1-Pad12)") (class "Default")
      (node (ref "X1") (pin "12") (pinfunction "12_12") (pintype "passive"))
    )
    (net (code "69") (name "unconnected-(X1-Pad14)") (class "Default")
      (node (ref "X1") (pin "14") (pinfunction "14_14") (pintype "passive"))
    )
    (net (code "70") (name "unconnected-(X1-Pad16)") (class "Default")
      (node (ref "X1") (pin "16") (pinfunction "16_16") (pintype "passive"))
    )
    (net (code "71") (name "unconnected-(X1-Pad18)") (class "Default")
      (node (ref "X1") (pin "18") (pinfunction "18_18") (pintype "passive"))
    )
    (net (code "72") (name "unconnected-(X1-Pad20)") (class "Default")
      (node (ref "X1") (pin "20") (pinfunction "20_20") (pintype "passive"))
    )
    (net (code "73") (name "unconnected-(X1-Pad22)") (class "Default")
      (node (ref "X1") (pin "22") (pinfunction "22_22") (pintype "passive"))
    )
    (net (code "74") (name "unconnected-(X1-Pad24)") (class "Default")
      (node (ref "X1") (pin "24") (pinfunction "24_24") (pintype "passive"))
    )
    (net (code "75") (name "unconnected-(X1-Pad26)") (class "Default")
      (node (ref "X1") (pin "26") (pinfunction "26_26") (pintype "passive"))
    )
    (net (code "76") (name "unconnected-(X1-Pad28)") (class "Default")
      (node (ref "X1") (pin "28") (pinfunction "28_28") (pintype "passive"))
    )
  )
)
